# Sheet4_1.net
KiCad netlist of a schematic drawn in Altium Designer
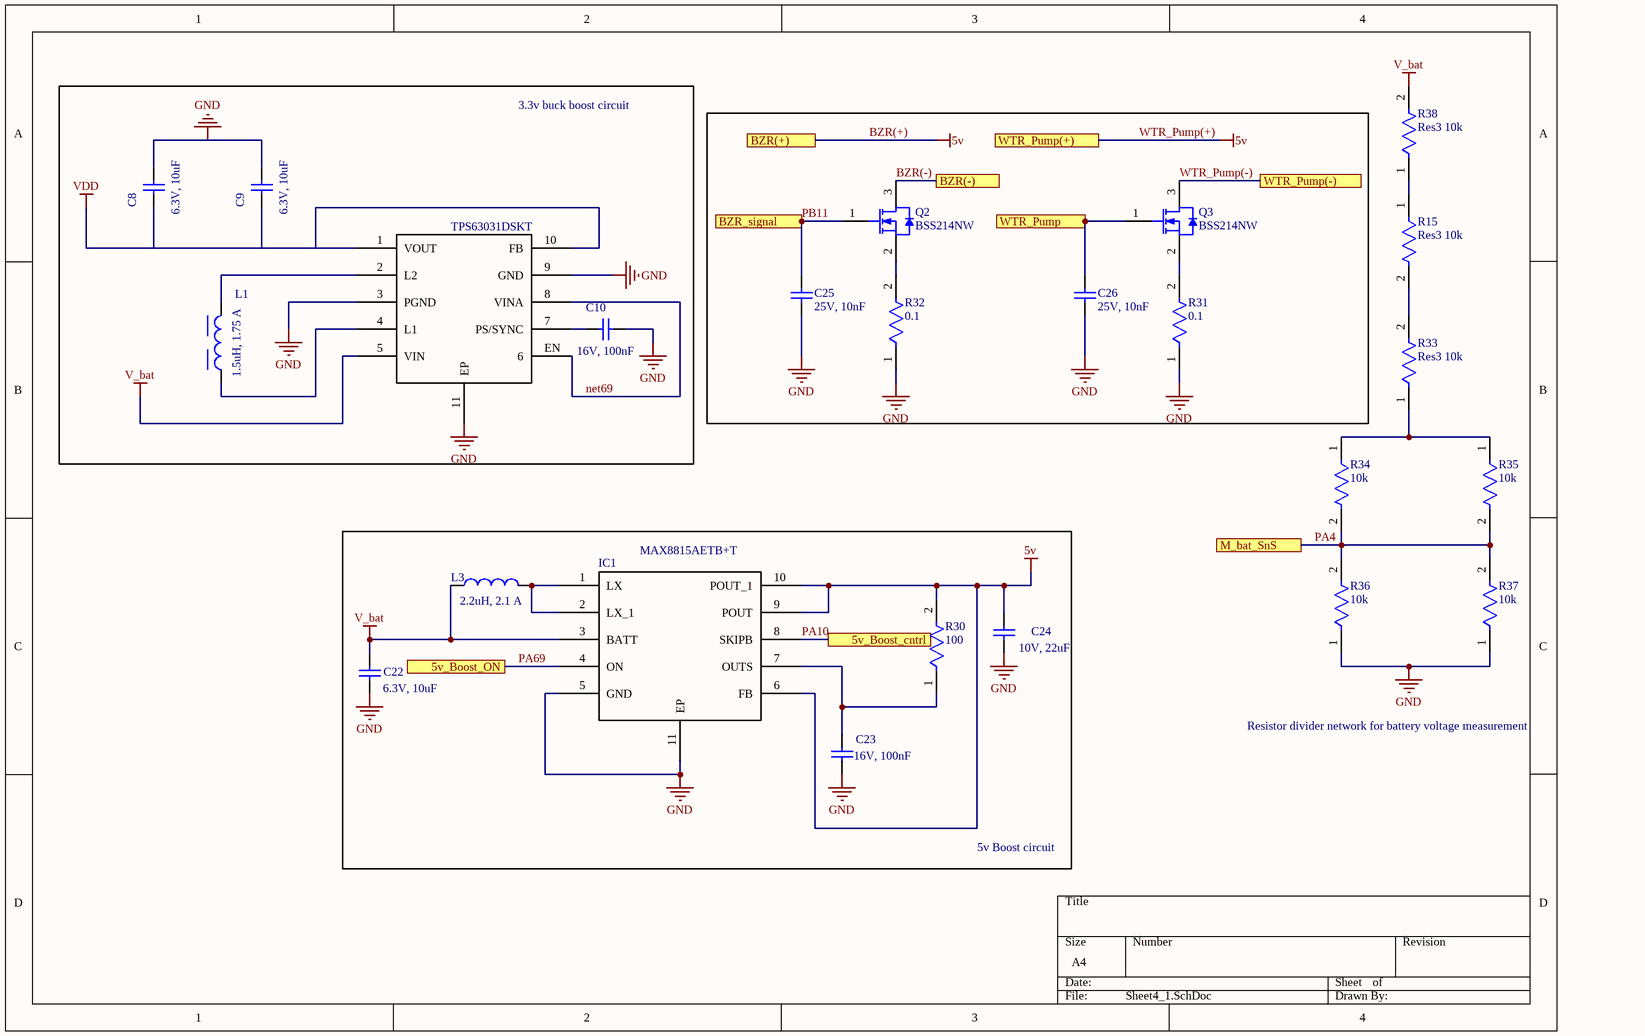
[diagram p0: Sheet4_1.SchDoc]

(export (version "E")
  (design (tool "Eeschema 10.0.6"))
  (components
    (comp (ref "C8")
      (value "6.3V, 10uF")
      (footprint "WCAP-CSGP_0603_L1.6W0.8H0.8_Reflow")
      (fields (field (name "TOLERANCE") "20%"))
      (libsource (lib "Altium Content Vault") (part "Capacitor_Non-Polarized"))
    )
    (comp (ref "C9")
      (value "6.3V, 10uF")
      (footprint "WCAP-CSGP_0603_L1.6W0.8H0.8_Reflow")
      (fields (field (name "TOLERANCE") "20%"))
      (libsource (lib "Altium Content Vault") (part "Capacitor_Non-Polarized"))
    )
    (comp (ref "C10")
      (value "16V, 100nF")
      (footprint "WCAP-CSGP_0603_L1.6W0.8H0.8_Reflow")
      (description "Cap Ceramic 0.1uF 16V X7R 10% Pad SMD 0603 125C T/R")
      (fields (field (name "TOLERANCE") "10%"))
      (libsource (lib "Altium Content Vault") (part "Capacitor_Non-Polarized"))
    )
    (comp (ref "C22")
      (value "6.3V, 10uF")
      (footprint "WCAP-CSGP_0603_L1.6W0.8H0.8_Reflow")
      (fields (field (name "TOLERANCE") "20%"))
      (libsource (lib "Altium Content Vault") (part "Capacitor_Non-Polarized"))
    )
    (comp (ref "C23")
      (value "16V, 100nF")
      (footprint "WCAP-CSGP_0603_L1.6W0.8H0.8_Reflow")
      (description "Cap Ceramic 0.1uF 16V X7R 10% Pad SMD 0603 125C T/R")
      (fields (field (name "TOLERANCE") "10%"))
      (libsource (lib "Altium Content Vault") (part "Capacitor_Non-Polarized"))
    )
    (comp (ref "C24")
      (value "10V, 22uF")
      (footprint "WCAP-CSGP_0805_L2W1.25H1.25")
      (description "Multilayer Ceramic Capacitor 22uF 0805 2")
      (fields (field (name "TOLERANCE") "20%"))
      (libsource (lib "Altium Content Vault") (part "Capacitor_Non-Polarized"))
    )
    (comp (ref "C25")
      (value "25V, 10nF")
      (footprint "CAPC2013X94X50LL20T25")
      (fields
        (field (name "MANUFACTURER") "AVX Interconnect / Elco")
        (field (name "PART NUMBER") "08053C103JAT2A")
      )
      (libsource (lib "Altium Content Vault") (part "CAP"))
    )
    (comp (ref "C26")
      (value "25V, 10nF")
      (footprint "CAPC2013X94X50LL20T25")
      (fields
        (field (name "MANUFACTURER") "AVX Interconnect / Elco")
        (field (name "PART NUMBER") "08053C103JAT2A")
      )
      (libsource (lib "Altium Content Vault") (part "CAP"))
    )
    (comp (ref "IC1")
      (value "MAX8815AETB+T")
      (footprint "21-0137I_T1033+2_MXM")
      (libsource (lib "Schlib1") (part "MAX8815AETB+T"))
    )
    (comp (ref "L1")
      (value "1.5uH, 1.75 A")
      (footprint "WE-TPC_3816")
      (description "100KHz 125MHz 1.55A 1.75A 1.5μH 47mΩ ±30% standard mounting，SMD mount 3.8mm*3.8mm*1.8mm")
      (fields (field (name "TOLERANCE") "30%"))
      (libsource (lib "Altium Content Vault") (part "Inductor - 3"))
    )
    (comp (ref "L3")
      (value "2.2uH, 2.1 A")
      (footprint "WE-PMCI_322512")
      (description "We-pmci Series 2.2 Uh Multilayer SMD Inductor, 1210 Case, 25MHZ 2.1A 106MO")
      (fields (field (name "TOLERANCE") "20%"))
      (libsource (lib "Altium Content Vault") (part "Inductor - 1"))
    )
    (comp (ref "Q2")
      (value "BSS214NW")
      (footprint "INF-PG-SOT-323_N")
      (fields (field (name "MANUFACTURER") "Infineon"))
      (libsource (lib "Altium Content Vault") (part "INF-NEMOS-GSD-3"))
    )
    (comp (ref "Q3")
      (value "BSS214NW")
      (footprint "INF-PG-SOT-323_N")
      (fields (field (name "MANUFACTURER") "Infineon"))
      (libsource (lib "Altium Content Vault") (part "INF-NEMOS-GSD-3"))
    )
    (comp (ref "R15")
      (value "Res3 10k")
      (footprint "FP-MCT0603-MFG")
      (description "RES SMD 100 OHM 1% 1/8W 0603")
      (libsource (lib "Altium Content Vault") (part "1029c3af85768c4190bb7ad29bc67b5"))
    )
    (comp (ref "R30")
      (value "100")
      (footprint "FP-RT0603-MFG")
      (description "RES SMD 100 OHM 0.1% 1/10W 0603")
      (fields
        (field (name "MANUFACTURER") "Yageo")
        (field (name "MANUFACTURER PART NUMBER") "RT0603BRE07100RL")
      )
      (libsource (lib "Altium Content Vault") (part "1029c3af85768c4190bb7ad29bc67b5"))
    )
    (comp (ref "R31")
      (value "0.1")
      (footprint "FP-RL0603-0_55-MFG")
      (description "RES 0.1 OHM 1% 1/10W 0603")
      (fields (field (name "TOLERANCE") "1%"))
      (libsource (lib "Altium Content Vault") (part "1029c3af85768c4190bb7ad29bc67b5"))
    )
    (comp (ref "R32")
      (value "0.1")
      (footprint "FP-RL0603-0_55-MFG")
      (description "RES 0.1 OHM 1% 1/10W 0603")
      (fields (field (name "TOLERANCE") "1%"))
      (libsource (lib "Altium Content Vault") (part "1029c3af85768c4190bb7ad29bc67b5"))
    )
    (comp (ref "R33")
      (value "Res3 10k")
      (footprint "FP-MCT0603-IPC_B")
      (description "RES SMD 100 OHM 1% 1/8W 0603")
      (libsource (lib "Altium Content Vault") (part "1029c3af85768c4190bb7ad29bc67b5"))
    )
    (comp (ref "R34")
      (value "10k")
      (footprint "FP-MCT0603-MFG")
      (description "RES SMD 100 OHM 1% 1/8W 0603")
      (libsource (lib "Altium Content Vault") (part "1029c3af85768c4190bb7ad29bc67b5"))
    )
    (comp (ref "R35")
      (value "10k")
      (footprint "FP-MCT0603-MFG")
      (description "RES SMD 100 OHM 1% 1/8W 0603")
      (libsource (lib "Altium Content Vault") (part "1029c3af85768c4190bb7ad29bc67b5"))
    )
    (comp (ref "R36")
      (value "10k")
      (footprint "FP-MCT0603-MFG")
      (description "RES SMD 100 OHM 1% 1/8W 0603")
      (libsource (lib "Altium Content Vault") (part "1029c3af85768c4190bb7ad29bc67b5"))
    )
    (comp (ref "R37")
      (value "10k")
      (footprint "FP-MCT0603-MFG")
      (description "RES SMD 100 OHM 1% 1/8W 0603")
      (libsource (lib "Altium Content Vault") (part "1029c3af85768c4190bb7ad29bc67b5"))
    )
    (comp (ref "R38")
      (value "Res3 10k")
      (footprint "FP-MCT0603-MFG")
      (description "RES SMD 100 OHM 1% 1/8W 0603")
      (libsource (lib "Altium Content Vault") (part "1029c3af85768c4190bb7ad29bc67b5"))
    )
    (comp (ref "U3")
      (value "TPS63031DSKT")
      (footprint "TPS63031DSKT")
      (description "High Efficient Single Inductor Buck-Boost Converter with 1-A Switches 10-SON -40 to 125")
      (libsource (lib "Schlib1") (part "TPS63031DSKT"))
    )
  )
  (nets
    (net (code "1") (name "/BZR(-)") (class "Default")
      (node (ref "Q2") (pin "3") (pinfunction "DRAIN_3") (pintype "passive"))
    )
    (net (code "2") (name "/PA4") (class "Default")
      (node (ref "R34") (pin "2") (pinfunction "2_2") (pintype "passive"))
      (node (ref "R35") (pin "2") (pinfunction "2_2") (pintype "passive"))
      (node (ref "R36") (pin "2") (pinfunction "2_2") (pintype "passive"))
      (node (ref "R37") (pin "2") (pinfunction "2_2") (pintype "passive"))
    )
    (net (code "3") (name "/PA10") (class "Default")
      (node (ref "IC1") (pin "8") (pinfunction "SKIPB_8") (pintype "passive"))
    )
    (net (code "4") (name "/PA69") (class "Default")
      (node (ref "IC1") (pin "4") (pinfunction "ON_4") (pintype "passive"))
    )
    (net (code "5") (name "/PB11") (class "Default")
      (node (ref "C25") (pin "2") (pinfunction "2_2") (pintype "passive"))
      (node (ref "Q2") (pin "1") (pinfunction "GATE_1") (pintype "passive"))
    )
    (net (code "6") (name "/WTR_Pump") (class "Default")
      (node (ref "C26") (pin "2") (pinfunction "2_2") (pintype "passive"))
      (node (ref "Q3") (pin "1") (pinfunction "GATE_1") (pintype "passive"))
    )
    (net (code "7") (name "/WTR_Pump(-)") (class "Default")
      (node (ref "Q3") (pin "3") (pinfunction "DRAIN_3") (pintype "passive"))
    )
    (net (code "8") (name "/net69") (class "Default")
      (node (ref "U3") (pin "8") (pinfunction "VINA_8") (pintype "passive"))
      (node (ref "U3") (pin "EN") (pinfunction "6_EN") (pintype "passive"))
    )
    (net (code "9") (name "5v") (class "Default")
      (node (ref "C24") (pin "2") (pinfunction "2_2") (pintype "passive"))
      (node (ref "IC1") (pin "10") (pinfunction "POUT_1_10") (pintype "passive"))
      (node (ref "IC1") (pin "6") (pinfunction "FB_6") (pintype "passive"))
      (node (ref "IC1") (pin "9") (pinfunction "POUT_9") (pintype "passive"))
      (node (ref "R30") (pin "2") (pinfunction "2_2") (pintype "passive"))
    )
    (net (code "10") (name "GND") (class "Default")
      (node (ref "C10") (pin "2") (pinfunction "2_2") (pintype "passive"))
      (node (ref "C22") (pin "1") (pinfunction "1_1") (pintype "passive"))
      (node (ref "C23") (pin "1") (pinfunction "1_1") (pintype "passive"))
      (node (ref "C24") (pin "1") (pinfunction "1_1") (pintype "passive"))
      (node (ref "C25") (pin "1") (pinfunction "1_1") (pintype "passive"))
      (node (ref "C26") (pin "1") (pinfunction "1_1") (pintype "passive"))
      (node (ref "C8") (pin "2") (pinfunction "2_2") (pintype "passive"))
      (node (ref "C9") (pin "2") (pinfunction "2_2") (pintype "passive"))
      (node (ref "IC1") (pin "11") (pinfunction "EP_11") (pintype "passive"))
      (node (ref "IC1") (pin "5") (pinfunction "GND_5") (pintype "passive"))
      (node (ref "R31") (pin "1") (pinfunction "1_1") (pintype "passive"))
      (node (ref "R32") (pin "1") (pinfunction "1_1") (pintype "passive"))
      (node (ref "R36") (pin "1") (pinfunction "1_1") (pintype "passive"))
      (node (ref "R37") (pin "1") (pinfunction "1_1") (pintype "passive"))
      (node (ref "U3") (pin "11") (pinfunction "EP_11") (pintype "passive"))
      (node (ref "U3") (pin "3") (pinfunction "PGND_3") (pintype "passive"))
      (node (ref "U3") (pin "9") (pinfunction "GND_9") (pintype "passive"))
    )
    (net (code "11") (name "Net-(IC1-LX)") (class "Default")
      (node (ref "IC1") (pin "1") (pinfunction "LX_1") (pintype "passive"))
      (node (ref "IC1") (pin "2") (pinfunction "LX_1_2") (pintype "passive"))
      (node (ref "L3") (pin "2") (pinfunction "2_2") (pintype "passive"))
    )
    (net (code "12") (name "Net-(IC1-OUTS)") (class "Default")
      (node (ref "C23") (pin "2") (pinfunction "2_2") (pintype "passive"))
      (node (ref "IC1") (pin "7") (pinfunction "OUTS_7") (pintype "passive"))
      (node (ref "R30") (pin "1") (pinfunction "1_1") (pintype "passive"))
    )
    (net (code "13") (name "Net-(Q2-SOURCE)") (class "Default")
      (node (ref "Q2") (pin "2") (pinfunction "SOURCE_2") (pintype "passive"))
      (node (ref "R32") (pin "2") (pinfunction "2_2") (pintype "passive"))
    )
    (net (code "14") (name "Net-(Q3-SOURCE)") (class "Default")
      (node (ref "Q3") (pin "2") (pinfunction "SOURCE_2") (pintype "passive"))
      (node (ref "R31") (pin "2") (pinfunction "2_2") (pintype "passive"))
    )
    (net (code "15") (name "Net-(R15-Pad1)") (class "Default")
      (node (ref "R15") (pin "1") (pinfunction "1_1") (pintype "passive"))
      (node (ref "R38") (pin "1") (pinfunction "1_1") (pintype "passive"))
    )
    (net (code "16") (name "Net-(R15-Pad2)") (class "Default")
      (node (ref "R15") (pin "2") (pinfunction "2_2") (pintype "passive"))
      (node (ref "R33") (pin "2") (pinfunction "2_2") (pintype "passive"))
    )
    (net (code "17") (name "Net-(R33-Pad1)") (class "Default")
      (node (ref "R33") (pin "1") (pinfunction "1_1") (pintype "passive"))
      (node (ref "R34") (pin "1") (pinfunction "1_1") (pintype "passive"))
      (node (ref "R35") (pin "1") (pinfunction "1_1") (pintype "passive"))
    )
    (net (code "18") (name "Net-(U3-L1)") (class "Default")
      (node (ref "L1") (pin "1") (pinfunction "1_1") (pintype "passive"))
      (node (ref "U3") (pin "4") (pinfunction "L1_4") (pintype "passive"))
    )
    (net (code "19") (name "Net-(U3-L2)") (class "Default")
      (node (ref "L1") (pin "2") (pinfunction "2_2") (pintype "passive"))
      (node (ref "U3") (pin "2") (pinfunction "L2_2") (pintype "passive"))
    )
    (net (code "20") (name "Net-(U3-PS{slash}SYNC)") (class "Default")
      (node (ref "C10") (pin "1") (pinfunction "1_1") (pintype "passive"))
      (node (ref "U3") (pin "7") (pinfunction "PS/SYNC_7") (pintype "passive"))
    )
    (net (code "21") (name "VDD") (class "Default")
      (node (ref "C8") (pin "1") (pinfunction "1_1") (pintype "passive"))
      (node (ref "C9") (pin "1") (pinfunction "1_1") (pintype "passive"))
      (node (ref "U3") (pin "1") (pinfunction "VOUT_1") (pintype "passive"))
      (node (ref "U3") (pin "10") (pinfunction "FB_10") (pintype "passive"))
    )
    (net (code "22") (name "V_bat") (class "Default")
      (node (ref "C22") (pin "2") (pinfunction "2_2") (pintype "passive"))
      (node (ref "IC1") (pin "3") (pinfunction "BATT_3") (pintype "passive"))
      (node (ref "L3") (pin "1") (pinfunction "1_1") (pintype "passive"))
      (node (ref "R38") (pin "2") (pinfunction "2_2") (pintype "passive"))
      (node (ref "U3") (pin "5") (pinfunction "VIN_5") (pintype "passive"))
    )
  )
)
